# DSO_Trig.net
KiCad netlist of a schematic drawn in Altium Designer
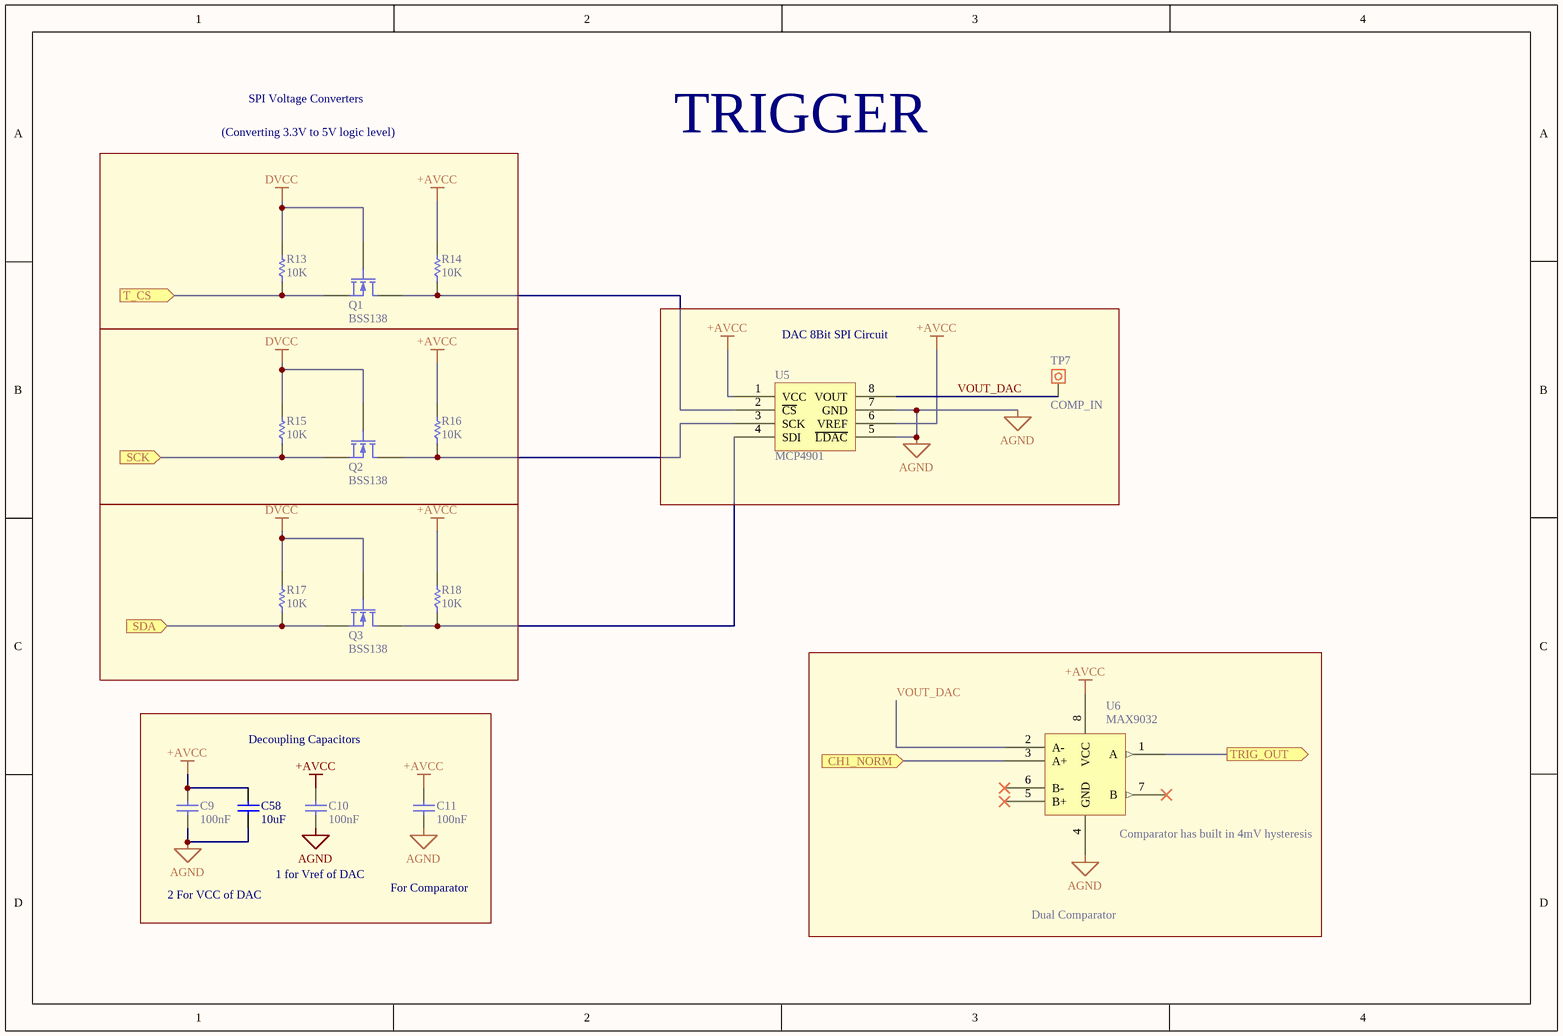
[diagram p0: DSO_Trig.SchDoc]

(export (version "E")
  (design (tool "Eeschema 10.0.6"))
  (components
    (comp (ref "C9")
      (value "100nF")
      (footprint "0805C")
      (description "Capacitor")
      (fields (field (name "REVIEWED BY") "RM - 2018/08/05"))
      (libsource (lib "DSO") (part "C"))
    )
    (comp (ref "C10")
      (value "100nF")
      (footprint "0805C")
      (description "Capacitor")
      (fields (field (name "REVIEWED BY") "RM - 2018/08/05"))
      (libsource (lib "DSO") (part "C"))
    )
    (comp (ref "C11")
      (value "100nF")
      (footprint "0805C")
      (description "Capacitor")
      (fields (field (name "REVIEWED BY") "RM - 2018/08/05"))
      (libsource (lib "DSO") (part "C"))
    )
    (comp (ref "C58")
      (value "10uF")
      (footprint "0805C")
      (description "Capacitor")
      (fields (field (name "REVIEWED BY") "RM - 2018/08/05"))
      (libsource (lib "DSO") (part "C"))
    )
    (comp (ref "Q1")
      (value "BSS138")
      (footprint "SOT23")
      (description "N-Channel MOSFET")
      (fields (field (name "PUBLISHER") "Altium Limited"))
      (libsource (lib "DSO") (part "MOSFET-N"))
    )
    (comp (ref "Q2")
      (value "BSS138")
      (footprint "SOT23")
      (description "N-Channel MOSFET")
      (fields (field (name "PUBLISHER") "Altium Limited"))
      (libsource (lib "DSO") (part "MOSFET-N"))
    )
    (comp (ref "Q3")
      (value "BSS138")
      (footprint "SOT23")
      (description "N-Channel MOSFET")
      (fields (field (name "PUBLISHER") "Altium Limited"))
      (libsource (lib "DSO") (part "MOSFET-N"))
    )
    (comp (ref "R13")
      (value "10K")
      (footprint "0805")
      (description "Resistor")
      (fields (field (name "REVIEWED BY") "RM - 2018/08/05"))
      (libsource (lib "DSO") (part "R"))
    )
    (comp (ref "R14")
      (value "10K")
      (footprint "0805")
      (description "Resistor")
      (fields (field (name "REVIEWED BY") "RM - 2018/08/05"))
      (libsource (lib "DSO") (part "R"))
    )
    (comp (ref "R15")
      (value "10K")
      (footprint "0805")
      (description "Resistor")
      (fields (field (name "REVIEWED BY") "RM - 2018/08/05"))
      (libsource (lib "DSO") (part "R"))
    )
    (comp (ref "R16")
      (value "10K")
      (footprint "0805")
      (description "Resistor")
      (fields (field (name "REVIEWED BY") "RM - 2018/08/05"))
      (libsource (lib "DSO") (part "R"))
    )
    (comp (ref "R17")
      (value "10K")
      (footprint "0805")
      (description "Resistor")
      (fields (field (name "REVIEWED BY") "RM - 2018/08/05"))
      (libsource (lib "DSO") (part "R"))
    )
    (comp (ref "R18")
      (value "10K")
      (footprint "0805")
      (description "Resistor")
      (fields (field (name "REVIEWED BY") "RM - 2018/08/05"))
      (libsource (lib "DSO") (part "R"))
    )
    (comp (ref "TP7")
      (value "COMP_IN")
      (footprint "Testpoin")
      (description "Pad")
      (fields (field (name "Comment") "INPUT"))
      (libsource (lib "DSO") (part "Test Point"))
    )
    (comp (ref "U5")
      (value "MCP4901")
      (footprint "SOIC-8")
      (description "DAC 8bit SPI")
      (fields (field (name "REVIEWED BY") "RM - 2018/08/05"))
      (libsource (lib "DSO") (part "MCP4901"))
    )
    (comp (ref "U6")
      (value "MAX9032")
      (footprint "SOIC-8")
      (description "Dual Comparator")
      (fields (field (name "REVIEWED BY") "RM - 2018/08/05"))
      (libsource (lib "DSO") (part "MAX9032"))
    )
  )
  (nets
    (net (code "1") (name "+AVCC") (class "Default")
      (node (ref "C10") (pin "1") (pinfunction "1_1") (pintype "passive"))
      (node (ref "C11") (pin "1") (pinfunction "1_1") (pintype "passive"))
      (node (ref "C58") (pin "1") (pinfunction "1_1") (pintype "passive"))
      (node (ref "C9") (pin "1") (pinfunction "1_1") (pintype "passive"))
      (node (ref "R14") (pin "2") (pintype "passive"))
      (node (ref "R16") (pin "2") (pintype "passive"))
      (node (ref "R18") (pin "2") (pintype "passive"))
      (node (ref "U5") (pin "1") (pinfunction "VCC_1") (pintype "passive"))
      (node (ref "U5") (pin "6") (pinfunction "VREF_6") (pintype "passive"))
      (node (ref "U6") (pin "8") (pinfunction "VCC_8") (pintype "passive"))
    )
    (net (code "2") (name "/CH1_NORM") (class "Default")
      (node (ref "U6") (pin "3") (pinfunction "A+_3") (pintype "passive"))
    )
    (net (code "3") (name "/SCK") (class "Default")
      (node (ref "Q2") (pin "2") (pinfunction "2_2") (pintype "passive"))
      (node (ref "R15") (pin "1") (pintype "passive"))
    )
    (net (code "4") (name "/SDA") (class "Default")
      (node (ref "Q3") (pin "2") (pinfunction "2_2") (pintype "passive"))
      (node (ref "R17") (pin "1") (pintype "passive"))
    )
    (net (code "5") (name "/TRIG_OUT") (class "Default")
      (node (ref "U6") (pin "1") (pinfunction "A_1") (pintype "output"))
    )
    (net (code "6") (name "/T_CS") (class "Default")
      (node (ref "Q1") (pin "2") (pinfunction "2_2") (pintype "passive"))
      (node (ref "R13") (pin "1") (pintype "passive"))
    )
    (net (code "7") (name "/VOUT_DAC") (class "Default")
      (node (ref "TP7") (pin "1") (pintype "passive"))
      (node (ref "U5") (pin "8") (pinfunction "VOUT_8") (pintype "passive"))
      (node (ref "U6") (pin "2") (pinfunction "A-_2") (pintype "passive"))
    )
    (net (code "8") (name "AGND") (class "Default")
      (node (ref "C10") (pin "2") (pinfunction "2_2") (pintype "passive"))
      (node (ref "C11") (pin "2") (pinfunction "2_2") (pintype "passive"))
      (node (ref "C58") (pin "2") (pinfunction "2_2") (pintype "passive"))
      (node (ref "C9") (pin "2") (pinfunction "2_2") (pintype "passive"))
      (node (ref "U5") (pin "5") (pinfunction "~{LDAC}_5") (pintype "passive"))
      (node (ref "U5") (pin "7") (pinfunction "GND_7") (pintype "passive"))
      (node (ref "U6") (pin "4") (pinfunction "GND_4") (pintype "passive"))
    )
    (net (code "9") (name "DVCC") (class "Default")
      (node (ref "Q1") (pin "1") (pinfunction "1_1") (pintype "passive"))
      (node (ref "Q2") (pin "1") (pinfunction "1_1") (pintype "passive"))
      (node (ref "Q3") (pin "1") (pinfunction "1_1") (pintype "passive"))
      (node (ref "R13") (pin "2") (pintype "passive"))
      (node (ref "R15") (pin "2") (pintype "passive"))
      (node (ref "R17") (pin "2") (pintype "passive"))
    )
    (net (code "10") (name "Net-(U5-SCK)") (class "Default")
      (node (ref "Q2") (pin "3") (pinfunction "3_3") (pintype "passive"))
      (node (ref "R16") (pin "1") (pintype "passive"))
      (node (ref "U5") (pin "3") (pinfunction "SCK_3") (pintype "passive"))
    )
    (net (code "11") (name "Net-(U5-SDI)") (class "Default")
      (node (ref "Q3") (pin "3") (pinfunction "3_3") (pintype "passive"))
      (node (ref "R18") (pin "1") (pintype "passive"))
      (node (ref "U5") (pin "4") (pinfunction "SDI_4") (pintype "passive"))
    )
    (net (code "12") (name "Net-(U5-~{CS})") (class "Default")
      (node (ref "Q1") (pin "3") (pinfunction "3_3") (pintype "passive"))
      (node (ref "R14") (pin "1") (pintype "passive"))
      (node (ref "U5") (pin "2") (pinfunction "~{CS}_2") (pintype "passive"))
    )
    (net (code "13") (name "unconnected-(U6-B+-Pad5)") (class "Default")
      (node (ref "U6") (pin "5") (pinfunction "B+_5") (pintype "passive+no_connect"))
    )
    (net (code "14") (name "unconnected-(U6-B--Pad6)") (class "Default")
      (node (ref "U6") (pin "6") (pinfunction "B-_6") (pintype "passive+no_connect"))
    )
    (net (code "15") (name "unconnected-(U6-B-Pad7)") (class "Default")
      (node (ref "U6") (pin "7") (pinfunction "B_7") (pintype "output+no_connect"))
    )
  )
)
